# Xmas_B_board.net
KiCad netlist of a schematic drawn in EAGLE
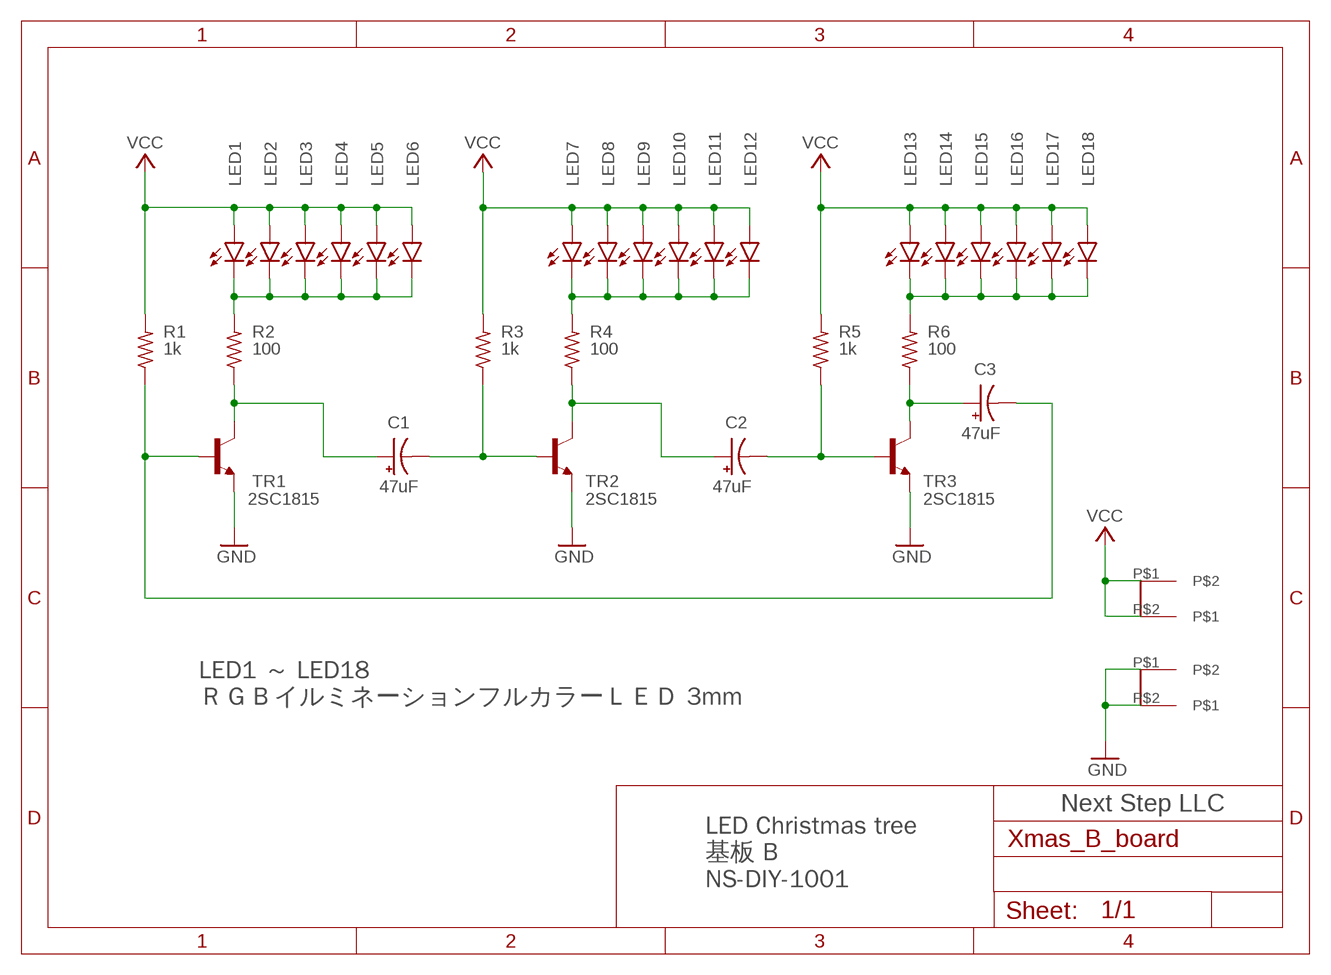
[diagram p0: schematic, sheet 1]

(export (version "E")
  (design (tool "Eeschema 10.0.6"))
  (components
    (comp (ref "C1")
      (value "47uF")
      (footprint "eagle-import:E2-4")
      (libsource (lib "eagle-import") (part "CPOL-USE2-4"))
    )
    (comp (ref "C2")
      (value "47uF")
      (footprint "eagle-import:E2-4")
      (libsource (lib "eagle-import") (part "CPOL-USE2-4"))
    )
    (comp (ref "C3")
      (value "47uF")
      (footprint "eagle-import:E2-4")
      (libsource (lib "eagle-import") (part "CPOL-USE2-4"))
    )
    (comp (ref "LED1")
      (value "LED3MM")
      (footprint "eagle-import:LED3MM")
      (libsource (lib "eagle-import") (part "LED3MM"))
    )
    (comp (ref "LED2")
      (value "LED3MM")
      (footprint "eagle-import:LED3MM")
      (libsource (lib "eagle-import") (part "LED3MM"))
    )
    (comp (ref "LED3")
      (value "LED3MM")
      (footprint "eagle-import:LED3MM")
      (libsource (lib "eagle-import") (part "LED3MM"))
    )
    (comp (ref "LED4")
      (value "LED3MM")
      (footprint "eagle-import:LED3MM")
      (libsource (lib "eagle-import") (part "LED3MM"))
    )
    (comp (ref "LED5")
      (value "LED3MM")
      (footprint "eagle-import:LED3MM")
      (libsource (lib "eagle-import") (part "LED3MM"))
    )
    (comp (ref "LED6")
      (value "LED3MM")
      (footprint "eagle-import:LED3MM")
      (libsource (lib "eagle-import") (part "LED3MM"))
    )
    (comp (ref "LED7")
      (value "LED3MM")
      (footprint "eagle-import:LED3MM")
      (libsource (lib "eagle-import") (part "LED3MM"))
    )
    (comp (ref "LED8")
      (value "LED3MM")
      (footprint "eagle-import:LED3MM")
      (libsource (lib "eagle-import") (part "LED3MM"))
    )
    (comp (ref "LED9")
      (value "LED3MM")
      (footprint "eagle-import:LED3MM")
      (libsource (lib "eagle-import") (part "LED3MM"))
    )
    (comp (ref "LED10")
      (value "LED3MM")
      (footprint "eagle-import:LED3MM")
      (libsource (lib "eagle-import") (part "LED3MM"))
    )
    (comp (ref "LED11")
      (value "LED3MM")
      (footprint "eagle-import:LED3MM")
      (libsource (lib "eagle-import") (part "LED3MM"))
    )
    (comp (ref "LED12")
      (value "LED3MM")
      (footprint "eagle-import:LED3MM")
      (libsource (lib "eagle-import") (part "LED3MM"))
    )
    (comp (ref "LED13")
      (value "LED3MM")
      (footprint "eagle-import:LED3MM")
      (libsource (lib "eagle-import") (part "LED3MM"))
    )
    (comp (ref "LED14")
      (value "LED3MM")
      (footprint "eagle-import:LED3MM")
      (libsource (lib "eagle-import") (part "LED3MM"))
    )
    (comp (ref "LED15")
      (value "LED3MM")
      (footprint "eagle-import:LED3MM")
      (libsource (lib "eagle-import") (part "LED3MM"))
    )
    (comp (ref "LED16")
      (value "LED3MM")
      (footprint "eagle-import:LED3MM")
      (libsource (lib "eagle-import") (part "LED3MM"))
    )
    (comp (ref "LED17")
      (value "LED3MM")
      (footprint "eagle-import:LED3MM")
      (libsource (lib "eagle-import") (part "LED3MM"))
    )
    (comp (ref "LED18")
      (value "LED3MM")
      (footprint "eagle-import:LED3MM")
      (libsource (lib "eagle-import") (part "LED3MM"))
    )
    (comp (ref "R1")
      (value "1k")
      (footprint "eagle-import:0204_7")
      (libsource (lib "eagle-import") (part "R-US_0204/7"))
    )
    (comp (ref "R2")
      (value "100")
      (footprint "eagle-import:0204_7")
      (libsource (lib "eagle-import") (part "R-US_0204/7"))
    )
    (comp (ref "R3")
      (value "1k")
      (footprint "eagle-import:0204_7")
      (libsource (lib "eagle-import") (part "R-US_0204/7"))
    )
    (comp (ref "R4")
      (value "100")
      (footprint "eagle-import:0204_7")
      (libsource (lib "eagle-import") (part "R-US_0204/7"))
    )
    (comp (ref "R5")
      (value "1k")
      (footprint "eagle-import:0204_7")
      (libsource (lib "eagle-import") (part "R-US_0204/7"))
    )
    (comp (ref "R6")
      (value "100")
      (footprint "eagle-import:0204_7")
      (libsource (lib "eagle-import") (part "R-US_0204/7"))
    )
    (comp (ref "TR1")
      (value "2SC1815")
      (footprint "eagle-import:TO92-ECB")
      (libsource (lib "eagle-import") (part "2SC1815"))
    )
    (comp (ref "TR2")
      (value "2SC1815")
      (footprint "eagle-import:TO92-ECB")
      (libsource (lib "eagle-import") (part "2SC1815"))
    )
    (comp (ref "TR3")
      (value "2SC1815")
      (footprint "eagle-import:TO92-ECB")
      (libsource (lib "eagle-import") (part "2SC1815"))
    )
    (comp (ref "U$1")
      (value "XMAS_POWER")
      (footprint "eagle-import:XMAS_POWER")
      (libsource (lib "eagle-import") (part "XMAS_POWER"))
    )
    (comp (ref "U$2")
      (value "XMAS_POWER")
      (footprint "eagle-import:XMAS_POWER")
      (libsource (lib "eagle-import") (part "XMAS_POWER"))
    )
  )
  (nets
    (net (code "1") (name "GND") (class "Default")
      (node (ref "TR1") (pin "E") (pinfunction "E_E") (pintype "passive"))
      (node (ref "TR2") (pin "E") (pinfunction "E_E") (pintype "passive"))
      (node (ref "TR3") (pin "E") (pinfunction "E_E") (pintype "passive"))
      (node (ref "U$2") (pin "P$1") (pinfunction "P$2_P$1") (pintype "bidirectional"))
      (node (ref "U$2") (pin "P$2") (pinfunction "P$1_P$2") (pintype "bidirectional"))
    )
    (net (code "2") (name "Net-(C1-Pad+)") (class "Default")
      (node (ref "C1") (pin "+") (pinfunction "+_+") (pintype "passive"))
      (node (ref "R2") (pin "1") (pinfunction "1_1") (pintype "passive"))
      (node (ref "TR1") (pin "C") (pinfunction "C_C") (pintype "passive"))
    )
    (net (code "3") (name "Net-(C1-Pad-)") (class "Default")
      (node (ref "C1") (pin "-") (pinfunction "-_-") (pintype "passive"))
      (node (ref "R3") (pin "1") (pinfunction "1_1") (pintype "passive"))
      (node (ref "TR2") (pin "B") (pinfunction "B_B") (pintype "passive"))
    )
    (net (code "4") (name "Net-(C2-Pad+)") (class "Default")
      (node (ref "C2") (pin "+") (pinfunction "+_+") (pintype "passive"))
      (node (ref "R4") (pin "1") (pinfunction "1_1") (pintype "passive"))
      (node (ref "TR2") (pin "C") (pinfunction "C_C") (pintype "passive"))
    )
    (net (code "5") (name "Net-(C2-Pad-)") (class "Default")
      (node (ref "C2") (pin "-") (pinfunction "-_-") (pintype "passive"))
      (node (ref "R5") (pin "1") (pinfunction "1_1") (pintype "passive"))
      (node (ref "TR3") (pin "B") (pinfunction "B_B") (pintype "passive"))
    )
    (net (code "6") (name "Net-(C3-Pad+)") (class "Default")
      (node (ref "C3") (pin "+") (pinfunction "+_+") (pintype "passive"))
      (node (ref "R6") (pin "1") (pinfunction "1_1") (pintype "passive"))
      (node (ref "TR3") (pin "C") (pinfunction "C_C") (pintype "passive"))
    )
    (net (code "7") (name "Net-(C3-Pad-)") (class "Default")
      (node (ref "C3") (pin "-") (pinfunction "-_-") (pintype "passive"))
      (node (ref "R1") (pin "1") (pinfunction "1_1") (pintype "passive"))
      (node (ref "TR1") (pin "B") (pinfunction "B_B") (pintype "passive"))
    )
    (net (code "8") (name "Net-(LED1-C)") (class "Default")
      (node (ref "LED1") (pin "K") (pinfunction "C_K") (pintype "passive"))
      (node (ref "LED2") (pin "K") (pinfunction "C_K") (pintype "passive"))
      (node (ref "LED3") (pin "K") (pinfunction "C_K") (pintype "passive"))
      (node (ref "LED4") (pin "K") (pinfunction "C_K") (pintype "passive"))
      (node (ref "LED5") (pin "K") (pinfunction "C_K") (pintype "passive"))
      (node (ref "LED6") (pin "K") (pinfunction "C_K") (pintype "passive"))
      (node (ref "R2") (pin "2") (pinfunction "2_2") (pintype "passive"))
    )
    (net (code "9") (name "Net-(LED10-C)") (class "Default")
      (node (ref "LED10") (pin "K") (pinfunction "C_K") (pintype "passive"))
      (node (ref "LED11") (pin "K") (pinfunction "C_K") (pintype "passive"))
      (node (ref "LED12") (pin "K") (pinfunction "C_K") (pintype "passive"))
      (node (ref "LED7") (pin "K") (pinfunction "C_K") (pintype "passive"))
      (node (ref "LED8") (pin "K") (pinfunction "C_K") (pintype "passive"))
      (node (ref "LED9") (pin "K") (pinfunction "C_K") (pintype "passive"))
      (node (ref "R4") (pin "2") (pinfunction "2_2") (pintype "passive"))
    )
    (net (code "10") (name "Net-(LED13-C)") (class "Default")
      (node (ref "LED13") (pin "K") (pinfunction "C_K") (pintype "passive"))
      (node (ref "LED14") (pin "K") (pinfunction "C_K") (pintype "passive"))
      (node (ref "LED15") (pin "K") (pinfunction "C_K") (pintype "passive"))
      (node (ref "LED16") (pin "K") (pinfunction "C_K") (pintype "passive"))
      (node (ref "LED17") (pin "K") (pinfunction "C_K") (pintype "passive"))
      (node (ref "LED18") (pin "K") (pinfunction "C_K") (pintype "passive"))
      (node (ref "R6") (pin "2") (pinfunction "2_2") (pintype "passive"))
    )
    (net (code "11") (name "VCC") (class "Default")
      (node (ref "LED1") (pin "A") (pinfunction "A_A") (pintype "passive"))
      (node (ref "LED10") (pin "A") (pinfunction "A_A") (pintype "passive"))
      (node (ref "LED11") (pin "A") (pinfunction "A_A") (pintype "passive"))
      (node (ref "LED12") (pin "A") (pinfunction "A_A") (pintype "passive"))
      (node (ref "LED13") (pin "A") (pinfunction "A_A") (pintype "passive"))
      (node (ref "LED14") (pin "A") (pinfunction "A_A") (pintype "passive"))
      (node (ref "LED15") (pin "A") (pinfunction "A_A") (pintype "passive"))
      (node (ref "LED16") (pin "A") (pinfunction "A_A") (pintype "passive"))
      (node (ref "LED17") (pin "A") (pinfunction "A_A") (pintype "passive"))
      (node (ref "LED18") (pin "A") (pinfunction "A_A") (pintype "passive"))
      (node (ref "LED2") (pin "A") (pinfunction "A_A") (pintype "passive"))
      (node (ref "LED3") (pin "A") (pinfunction "A_A") (pintype "passive"))
      (node (ref "LED4") (pin "A") (pinfunction "A_A") (pintype "passive"))
      (node (ref "LED5") (pin "A") (pinfunction "A_A") (pintype "passive"))
      (node (ref "LED6") (pin "A") (pinfunction "A_A") (pintype "passive"))
      (node (ref "LED7") (pin "A") (pinfunction "A_A") (pintype "passive"))
      (node (ref "LED8") (pin "A") (pinfunction "A_A") (pintype "passive"))
      (node (ref "LED9") (pin "A") (pinfunction "A_A") (pintype "passive"))
      (node (ref "R1") (pin "2") (pinfunction "2_2") (pintype "passive"))
      (node (ref "R3") (pin "2") (pinfunction "2_2") (pintype "passive"))
      (node (ref "R5") (pin "2") (pinfunction "2_2") (pintype "passive"))
      (node (ref "U$1") (pin "P$1") (pinfunction "P$2_P$1") (pintype "bidirectional"))
      (node (ref "U$1") (pin "P$2") (pinfunction "P$1_P$2") (pintype "bidirectional"))
    )
  )
)
